# 11__MOT_tCONTROL_LED_STATUS.net
KiCad netlist of a schematic drawn in Altium Designer
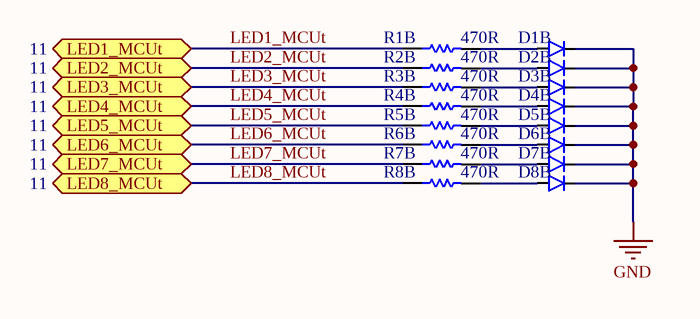
[diagram p0: [11]_MOT_tCONTROL LED STATUS.SchDoc]

(export (version "E")
  (design (tool "Eeschema 10.0.6"))
  (components
    (comp (ref "D1B") (value "LED 0603") (footprint "LED0603") (libsource (lib "DRIVER") (part "LED 0603")))
    (comp (ref "D2B") (value "LED 0603") (footprint "LED0603") (libsource (lib "DRIVER") (part "LED 0603")))
    (comp (ref "D3B") (value "LED 0603") (footprint "LED0603") (libsource (lib "DRIVER") (part "LED 0603")))
    (comp (ref "D4B") (value "LED 0603") (footprint "LED0603") (libsource (lib "DRIVER") (part "LED 0603")))
    (comp (ref "D5B") (value "LED 0603") (footprint "LED0603") (libsource (lib "DRIVER") (part "LED 0603")))
    (comp (ref "D6B") (value "LED 0603") (footprint "LED0603") (libsource (lib "DRIVER") (part "LED 0603")))
    (comp (ref "D7B") (value "LED 0603") (footprint "LED0603") (libsource (lib "DRIVER") (part "LED 0603")))
    (comp (ref "D8B") (value "LED 0603") (footprint "LED0603") (libsource (lib "DRIVER") (part "LED 0603")))
    (comp (ref "R1B")
      (value "470R")
      (footprint "res 0603")
      (description "RES SMD, 470 OHM 5% 1/8W 0603")
      (fields
        (field (name "MANUFACTURER1_PART#") "RK73B1JTTD471J")
        (field (name "MANUFACTURER2_PART#") "RMCF0603JT470R")
      )
      (libsource (lib "Full") (part "Res0.3"))
    )
    (comp (ref "R2B")
      (value "470R")
      (footprint "res 0603")
      (description "RES SMD, 470 OHM 5% 1/8W 0603")
      (fields
        (field (name "MANUFACTURER1_PART#") "RK73B1JTTD471J")
        (field (name "MANUFACTURER2_PART#") "RMCF0603JT470R")
      )
      (libsource (lib "Full") (part "Res0.3"))
    )
    (comp (ref "R3B")
      (value "470R")
      (footprint "res 0603")
      (description "RES SMD, 470 OHM 5% 1/8W 0603")
      (fields
        (field (name "MANUFACTURER1_PART#") "RK73B1JTTD471J")
        (field (name "MANUFACTURER2_PART#") "RMCF0603JT470R")
      )
      (libsource (lib "Full") (part "Res0.3"))
    )
    (comp (ref "R4B")
      (value "470R")
      (footprint "res 0603")
      (description "RES SMD, 470 OHM 5% 1/8W 0603")
      (fields
        (field (name "MANUFACTURER1_PART#") "RK73B1JTTD471J")
        (field (name "MANUFACTURER2_PART#") "RMCF0603JT470R")
      )
      (libsource (lib "Full") (part "Res0.3"))
    )
    (comp (ref "R5B")
      (value "470R")
      (footprint "res 0603")
      (description "RES SMD, 470 OHM 5% 1/8W 0603")
      (fields
        (field (name "MANUFACTURER1_PART#") "RK73B1JTTD471J")
        (field (name "MANUFACTURER2_PART#") "RMCF0603JT470R")
      )
      (libsource (lib "Full") (part "Res0.3"))
    )
    (comp (ref "R6B")
      (value "470R")
      (footprint "res 0603")
      (description "RES SMD, 470 OHM 5% 1/8W 0603")
      (fields
        (field (name "MANUFACTURER1_PART#") "RK73B1JTTD471J")
        (field (name "MANUFACTURER2_PART#") "RMCF0603JT470R")
      )
      (libsource (lib "Full") (part "Res0.3"))
    )
    (comp (ref "R7B")
      (value "470R")
      (footprint "res 0603")
      (description "RES SMD, 470 OHM 5% 1/8W 0603")
      (fields
        (field (name "MANUFACTURER1_PART#") "RK73B1JTTD471J")
        (field (name "MANUFACTURER2_PART#") "RMCF0603JT470R")
      )
      (libsource (lib "Full") (part "Res0.3"))
    )
    (comp (ref "R8B")
      (value "470R")
      (footprint "res 0603")
      (description "RES SMD, 470 OHM 5% 1/8W 0603")
      (fields
        (field (name "MANUFACTURER1_PART#") "RK73B1JTTD471J")
        (field (name "MANUFACTURER2_PART#") "RMCF0603JT470R")
      )
      (libsource (lib "Full") (part "Res0.3"))
    )
  )
  (nets
    (net (code "1") (name "/LED1_MCUt") (class "Default")
      (node (ref "R1B") (pin "1") (pinfunction "1_1") (pintype "passive"))
    )
    (net (code "2") (name "/LED2_MCUt") (class "Default")
      (node (ref "R2B") (pin "1") (pinfunction "1_1") (pintype "passive"))
    )
    (net (code "3") (name "/LED3_MCUt") (class "Default")
      (node (ref "R3B") (pin "1") (pinfunction "1_1") (pintype "passive"))
    )
    (net (code "4") (name "/LED4_MCUt") (class "Default")
      (node (ref "R4B") (pin "1") (pinfunction "1_1") (pintype "passive"))
    )
    (net (code "5") (name "/LED5_MCUt") (class "Default")
      (node (ref "R5B") (pin "1") (pinfunction "1_1") (pintype "passive"))
    )
    (net (code "6") (name "/LED6_MCUt") (class "Default")
      (node (ref "R6B") (pin "1") (pinfunction "1_1") (pintype "passive"))
    )
    (net (code "7") (name "/LED7_MCUt") (class "Default")
      (node (ref "R7B") (pin "1") (pinfunction "1_1") (pintype "passive"))
    )
    (net (code "8") (name "/LED8_MCUt") (class "Default")
      (node (ref "R8B") (pin "1") (pinfunction "1_1") (pintype "passive"))
    )
    (net (code "9") (name "GND") (class "Default")
      (node (ref "D1B") (pin "1") (pinfunction "K_1") (pintype "passive"))
      (node (ref "D2B") (pin "1") (pinfunction "K_1") (pintype "passive"))
      (node (ref "D3B") (pin "1") (pinfunction "K_1") (pintype "passive"))
      (node (ref "D4B") (pin "1") (pinfunction "K_1") (pintype "passive"))
      (node (ref "D5B") (pin "1") (pinfunction "K_1") (pintype "passive"))
      (node (ref "D6B") (pin "1") (pinfunction "K_1") (pintype "passive"))
      (node (ref "D7B") (pin "1") (pinfunction "K_1") (pintype "passive"))
      (node (ref "D8B") (pin "1") (pinfunction "K_1") (pintype "passive"))
    )
    (net (code "10") (name "Net-(D1B-A)") (class "Default")
      (node (ref "D1B") (pin "2") (pinfunction "A_2") (pintype "passive"))
      (node (ref "R1B") (pin "2") (pinfunction "2_2") (pintype "passive"))
    )
    (net (code "11") (name "Net-(D2B-A)") (class "Default")
      (node (ref "D2B") (pin "2") (pinfunction "A_2") (pintype "passive"))
      (node (ref "R2B") (pin "2") (pinfunction "2_2") (pintype "passive"))
    )
    (net (code "12") (name "Net-(D3B-A)") (class "Default")
      (node (ref "D3B") (pin "2") (pinfunction "A_2") (pintype "passive"))
      (node (ref "R3B") (pin "2") (pinfunction "2_2") (pintype "passive"))
    )
    (net (code "13") (name "Net-(D4B-A)") (class "Default")
      (node (ref "D4B") (pin "2") (pinfunction "A_2") (pintype "passive"))
      (node (ref "R4B") (pin "2") (pinfunction "2_2") (pintype "passive"))
    )
    (net (code "14") (name "Net-(D5B-A)") (class "Default")
      (node (ref "D5B") (pin "2") (pinfunction "A_2") (pintype "passive"))
      (node (ref "R5B") (pin "2") (pinfunction "2_2") (pintype "passive"))
    )
    (net (code "15") (name "Net-(D6B-A)") (class "Default")
      (node (ref "D6B") (pin "2") (pinfunction "A_2") (pintype "passive"))
      (node (ref "R6B") (pin "2") (pinfunction "2_2") (pintype "passive"))
    )
    (net (code "16") (name "Net-(D7B-A)") (class "Default")
      (node (ref "D7B") (pin "2") (pinfunction "A_2") (pintype "passive"))
      (node (ref "R7B") (pin "2") (pinfunction "2_2") (pintype "passive"))
    )
    (net (code "17") (name "Net-(D8B-A)") (class "Default")
      (node (ref "D8B") (pin "2") (pinfunction "A_2") (pintype "passive"))
      (node (ref "R8B") (pin "2") (pinfunction "2_2") (pintype "passive"))
    )
  )
)
